# utilidong-septic-sepic-lt1610-mk-1_1.net
KiCad netlist of a schematic drawn in EAGLE
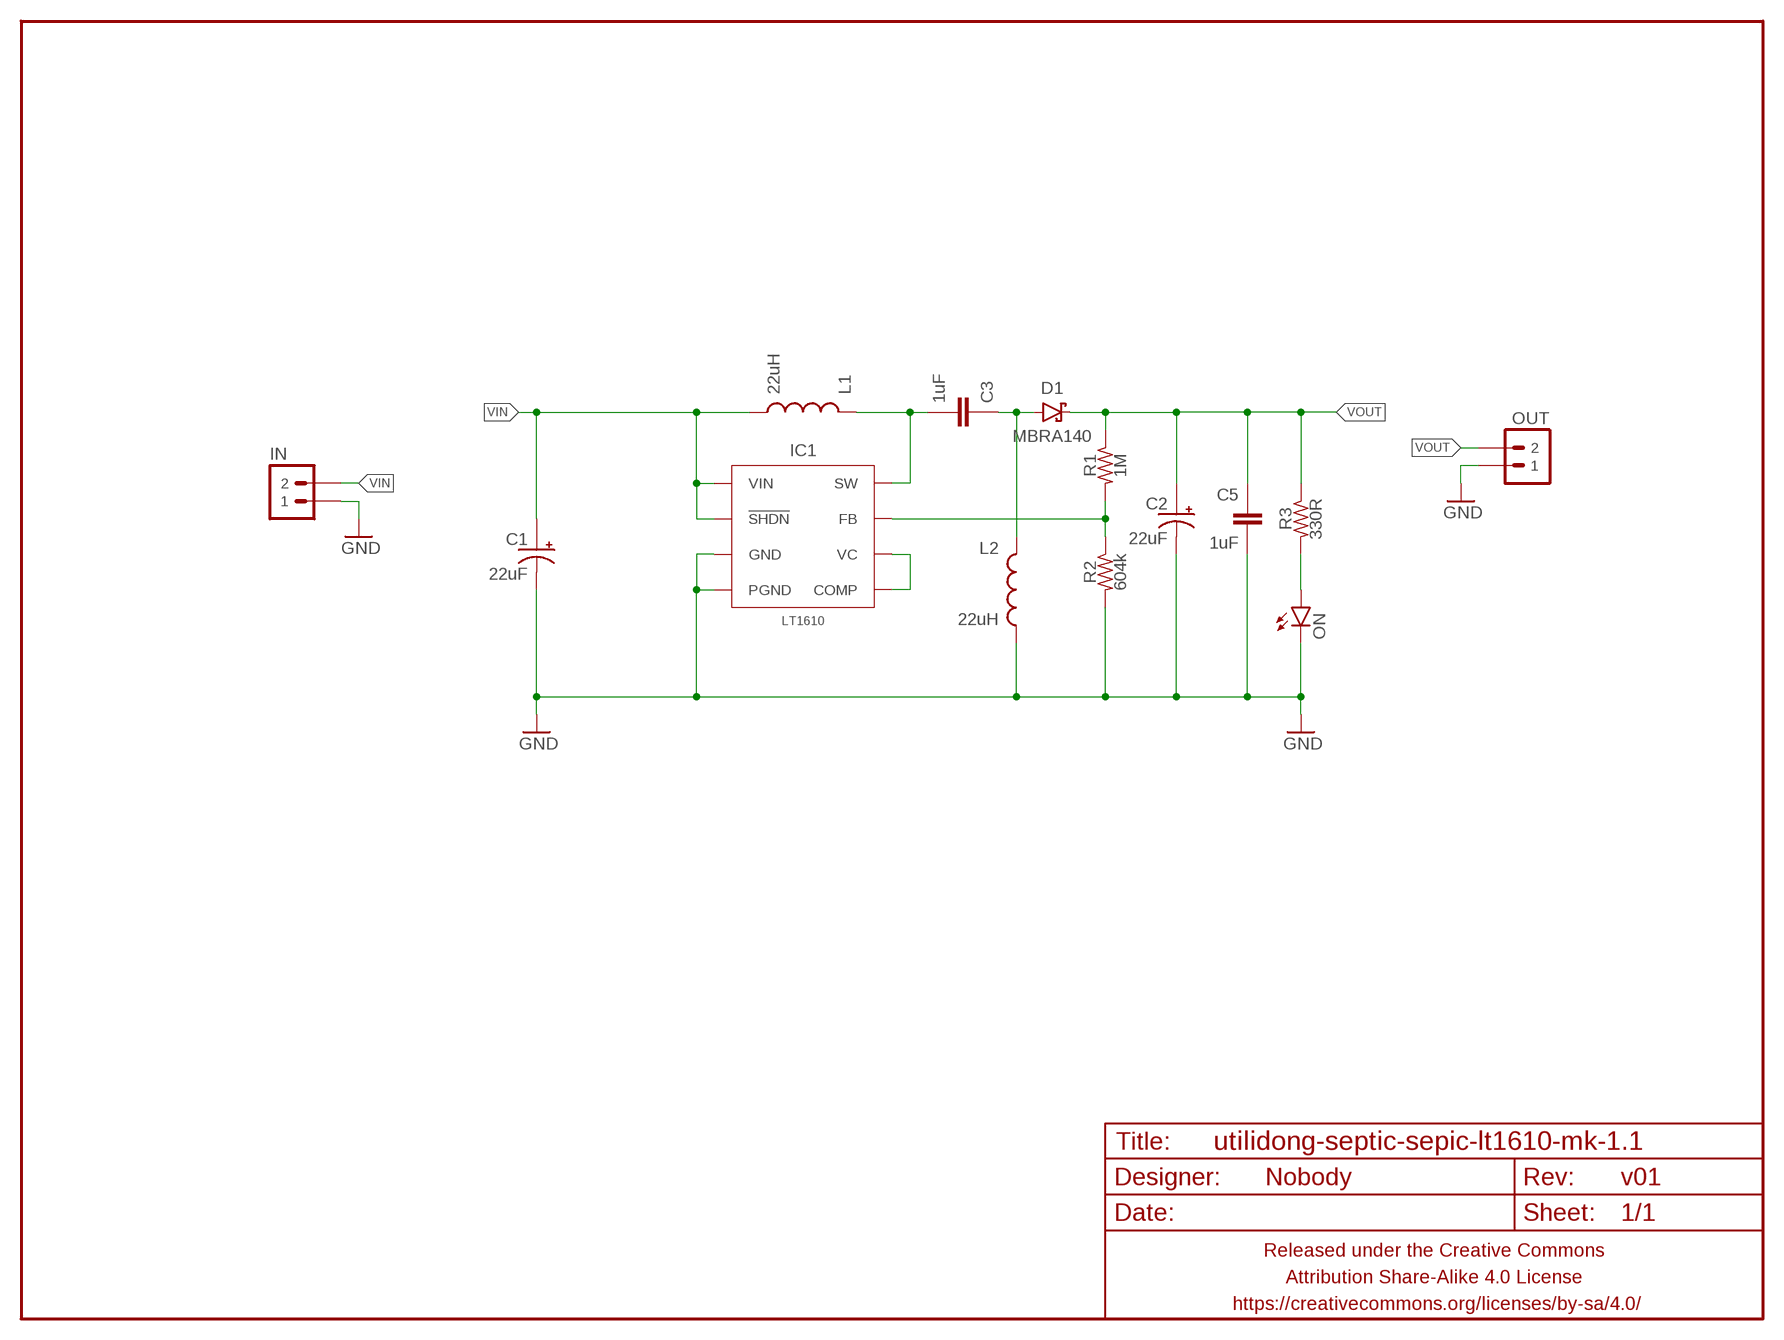
[diagram p0: schematic, sheet 1]

(export (version "E")
  (design (tool "Eeschema 10.0.6"))
  (components
    (comp (ref "C1")
      (value "22uF")
      (footprint "eagle-import:E2,5-6")
      (libsource (lib "eagle-import") (part "CAPACITOR-POLARIZEDE2.5-6"))
    )
    (comp (ref "C2")
      (value "22uF")
      (footprint "eagle-import:E2,5-6")
      (libsource (lib "eagle-import") (part "CAPACITOR-POLARIZEDE2.5-6"))
    )
    (comp (ref "C3")
      (value "1uF")
      (footprint "eagle-import:C0805")
      (libsource (lib "eagle-import") (part "CAPACITOR-CERAMICC0805"))
    )
    (comp (ref "C5")
      (value "1uF")
      (footprint "eagle-import:C0805")
      (libsource (lib "eagle-import") (part "CAPACITOR-CERAMICC0805"))
    )
    (comp (ref "D1")
      (value "MBRA140")
      (footprint "eagle-import:SMA-DIODE")
      (libsource (lib "eagle-import") (part "DIODE-SCHOTTKYMBRA140"))
    )
    (comp (ref "FRAME1")
      (value "FRAME-LETTERNO_PACKAGE")
      (footprint "eagle-import:DUMMY")
      (fields (field (name "DESIGNER") "Nobody"))
      (libsource (lib "eagle-import") (part "FRAME-LETTERNO_PACKAGE"))
    )
    (comp (ref "IC1")
      (value "LT1610")
      (footprint "eagle-import:SO08")
      (libsource (lib "eagle-import") (part "LT1610SOICN8"))
    )
    (comp (ref "IN")
      (value "M02PTH-CENTERED-R+")
      (footprint "eagle-import:1X02-CENTER-R+")
      (libsource (lib "eagle-import") (part "M02PTH-CENTERED-R+"))
    )
    (comp (ref "L1")
      (value "22uH")
      (footprint "eagle-import:MURATA-1100R")
      (libsource (lib "eagle-import") (part "INDUCTORMURATA-1100R"))
    )
    (comp (ref "L2")
      (value "22uH")
      (footprint "eagle-import:MURATA-1100R")
      (libsource (lib "eagle-import") (part "INDUCTORMURATA-1100R"))
    )
    (comp (ref "ON")
      (value "LED3MM-LESS")
      (footprint "eagle-import:LED3MM-LESSSILK")
      (libsource (lib "eagle-import") (part "LED3MM-LESS"))
    )
    (comp (ref "OUT")
      (value "M02PTH-CENTERED-R+")
      (footprint "eagle-import:1X02-CENTER-R+")
      (libsource (lib "eagle-import") (part "M02PTH-CENTERED-R+"))
    )
    (comp (ref "R1")
      (value "1M")
      (footprint "eagle-import:R0805")
      (libsource (lib "eagle-import") (part "RESISTORR0805"))
    )
    (comp (ref "R2")
      (value "604k")
      (footprint "eagle-import:R0805")
      (libsource (lib "eagle-import") (part "RESISTORR0805"))
    )
    (comp (ref "R3")
      (value "330R")
      (footprint "eagle-import:R0805")
      (libsource (lib "eagle-import") (part "RESISTORR0805"))
    )
  )
  (nets
    (net (code "1") (name "GND") (class "Default")
      (node (ref "C1") (pin "-") (pinfunction "-_-") (pintype "passive"))
      (node (ref "C2") (pin "-") (pinfunction "-_-") (pintype "passive"))
      (node (ref "C5") (pin "2") (pinfunction "2_2") (pintype "passive"))
      (node (ref "IC1") (pin "4") (pinfunction "PGND_4") (pintype "passive"))
      (node (ref "IC1") (pin "7") (pinfunction "GND_7") (pintype "passive"))
      (node (ref "IN") (pin "1") (pinfunction "1_1") (pintype "passive"))
      (node (ref "L2") (pin "P$2") (pinfunction "2_P$2") (pintype "passive"))
      (node (ref "ON") (pin "K") (pinfunction "C_K") (pintype "passive"))
      (node (ref "OUT") (pin "1") (pinfunction "1_1") (pintype "passive"))
      (node (ref "R2") (pin "2") (pinfunction "2_2") (pintype "passive"))
    )
    (net (code "2") (name "Net-(IC1-COMP)") (class "Default")
      (node (ref "IC1") (pin "1") (pinfunction "VC_1") (pintype "passive"))
      (node (ref "IC1") (pin "8") (pinfunction "COMP_8") (pintype "passive"))
    )
    (net (code "3") (name "Net-(IC1-FB)") (class "Default")
      (node (ref "IC1") (pin "2") (pinfunction "FB_2") (pintype "passive"))
      (node (ref "R1") (pin "2") (pinfunction "2_2") (pintype "passive"))
      (node (ref "R2") (pin "1") (pinfunction "1_1") (pintype "passive"))
    )
    (net (code "4") (name "Net-(IC1-SW)") (class "Default")
      (node (ref "C3") (pin "2") (pinfunction "2_2") (pintype "passive"))
      (node (ref "IC1") (pin "5") (pinfunction "SW_5") (pintype "passive"))
      (node (ref "L1") (pin "P$1") (pinfunction "1_P$1") (pintype "passive"))
    )
    (net (code "5") (name "Net-(L2-1)") (class "Default")
      (node (ref "C3") (pin "1") (pinfunction "1_1") (pintype "passive"))
      (node (ref "D1") (pin "A") (pinfunction "A_A") (pintype "passive"))
      (node (ref "L2") (pin "P$1") (pinfunction "1_P$1") (pintype "passive"))
    )
    (net (code "6") (name "Net-(ON-PadA)") (class "Default")
      (node (ref "ON") (pin "A") (pinfunction "A_A") (pintype "passive"))
      (node (ref "R3") (pin "2") (pinfunction "2_2") (pintype "passive"))
    )
    (net (code "7") (name "VIN") (class "Default")
      (node (ref "C1") (pin "+") (pinfunction "+_+") (pintype "passive"))
      (node (ref "IC1") (pin "3") (pinfunction "~{SHDN}_3") (pintype "passive"))
      (node (ref "IC1") (pin "6") (pinfunction "VIN_6") (pintype "passive"))
      (node (ref "IN") (pin "2") (pinfunction "2_2") (pintype "passive"))
      (node (ref "L1") (pin "P$2") (pinfunction "2_P$2") (pintype "passive"))
    )
    (net (code "8") (name "VOUT") (class "Default")
      (node (ref "C2") (pin "+") (pinfunction "+_+") (pintype "passive"))
      (node (ref "C5") (pin "1") (pinfunction "1_1") (pintype "passive"))
      (node (ref "D1") (pin "C") (pinfunction "C_C") (pintype "passive"))
      (node (ref "OUT") (pin "2") (pinfunction "2_2") (pintype "passive"))
      (node (ref "R1") (pin "1") (pinfunction "1_1") (pintype "passive"))
      (node (ref "R3") (pin "1") (pinfunction "1_1") (pintype "passive"))
    )
  )
)
